# Arduino_Mega2560.net
KiCad netlist of a schematic drawn in Altium Designer
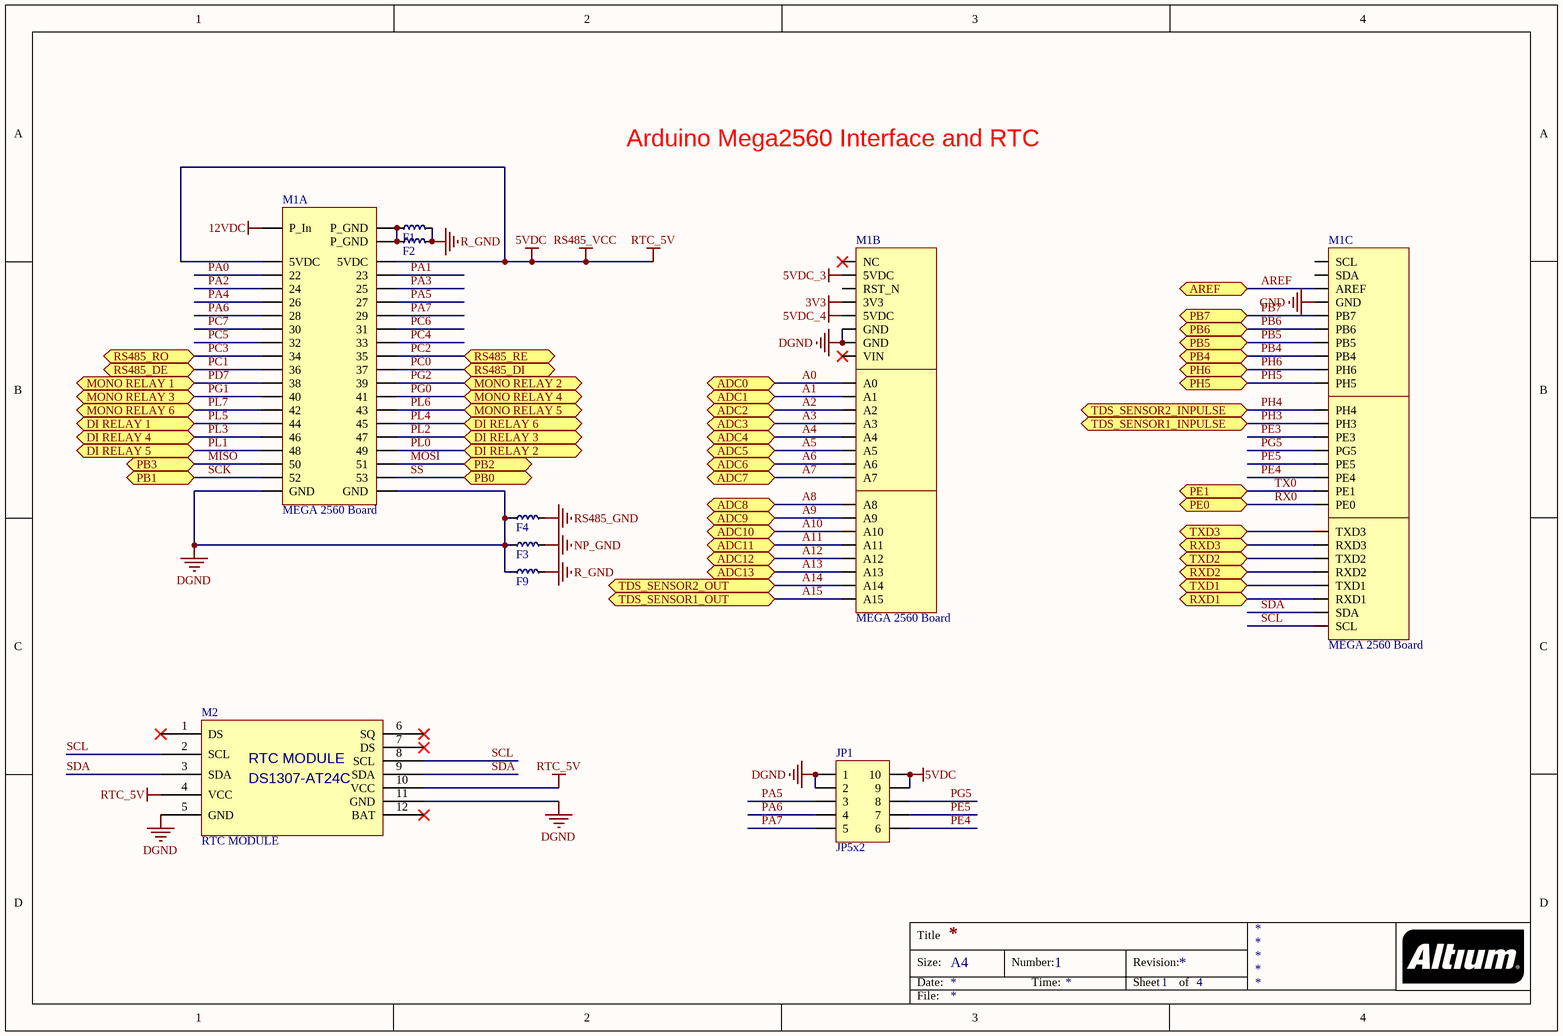
[diagram p0: Arduino_Mega2560.SchDoc]

(export (version "E")
  (design (tool "Eeschema 10.0.6"))
  (components
    (comp (ref "F1")
      (value "FBFB0805")
      (footprint "RESC_0603")
      (description "FERRITE BEAD 1000 OHM 0603")
      (libsource (lib "EngineersLife") (part "FB0603_1000Ohm"))
    )
    (comp (ref "F2")
      (value "FBFB0805")
      (footprint "RESC_0603")
      (description "FERRITE BEAD 1000 OHM 0603")
      (libsource (lib "EngineersLife") (part "FB0603_1000Ohm"))
    )
    (comp (ref "F3")
      (value "FBFB0805")
      (footprint "RESC_0603")
      (description "FERRITE BEAD 1000 OHM 0603")
      (libsource (lib "EngineersLife") (part "FB0603_1000Ohm"))
    )
    (comp (ref "F4")
      (value "FBFB0805")
      (footprint "RESC_0603")
      (description "FERRITE BEAD 1000 OHM 0603")
      (libsource (lib "EngineersLife") (part "FB0603_1000Ohm"))
    )
    (comp (ref "F9")
      (value "FBFB0805")
      (footprint "RESC_0603")
      (description "FERRITE BEAD 1000 OHM 0603")
      (libsource (lib "EngineersLife") (part "FB0603_1000Ohm"))
    )
    (comp (ref "JP1")
      (value "JP5x2")
      (footprint "JP5-D2T")
      (description "WR-PHD 2.54 mm Dual Socket Header")
      (fields
        (field (name "MANUFACTURER") "Würth Elektronik eiSos GmbH")
        (field (name "PARTNO") "61301021821")
        (field (name "CREATED BY") "Karrer Zheng")
      )
      (libsource (lib "EngineersLife") (part "JP5x2"))
    )
    (comp (ref "M1")
      (value "MEGA 2560 Board")
      (footprint "MEGA 2560")
      (description "Arduino ATMEGA 2560")
      (libsource (lib "EngineersLife") (part "MEGA 2560 Board"))
    )
    (comp (ref "M2")
      (value "RTC MODULE")
      (footprint "MODULE RTC DS1307-AT24C")
      (description "RTC DS1307-AT24C")
      (libsource (lib "EngineersLife") (part "RTC DS1307-AR24C"))
    )
  )
  (nets
    (net (code "1") (name "/A0") (class "Default")
      (node (ref "M1") (pin "A0") (pinfunction "A0_A0") (pintype "passive"))
    )
    (net (code "2") (name "/A1") (class "Default")
      (node (ref "M1") (pin "A1") (pinfunction "A1_A1") (pintype "passive"))
    )
    (net (code "3") (name "/A2") (class "Default")
      (node (ref "M1") (pin "A2") (pinfunction "A2_A2") (pintype "passive"))
    )
    (net (code "4") (name "/A3") (class "Default")
      (node (ref "M1") (pin "A3") (pinfunction "A3_A3") (pintype "passive"))
    )
    (net (code "5") (name "/A4") (class "Default")
      (node (ref "M1") (pin "A4") (pinfunction "A4_A4") (pintype "passive"))
    )
    (net (code "6") (name "/A5") (class "Default")
      (node (ref "M1") (pin "A5") (pinfunction "A5_A5") (pintype "passive"))
    )
    (net (code "7") (name "/A6") (class "Default")
      (node (ref "M1") (pin "A6") (pinfunction "A6_A6") (pintype "passive"))
    )
    (net (code "8") (name "/A7") (class "Default")
      (node (ref "M1") (pin "A7") (pinfunction "A7_A7") (pintype "passive"))
    )
    (net (code "9") (name "/A8") (class "Default")
      (node (ref "M1") (pin "A8") (pinfunction "A8_A8") (pintype "passive"))
    )
    (net (code "10") (name "/A9") (class "Default")
      (node (ref "M1") (pin "A9") (pinfunction "A9_A9") (pintype "passive"))
    )
    (net (code "11") (name "/A10") (class "Default")
      (node (ref "M1") (pin "A10") (pinfunction "A10_A10") (pintype "passive"))
    )
    (net (code "12") (name "/A11") (class "Default")
      (node (ref "M1") (pin "A11") (pinfunction "A11_A11") (pintype "passive"))
    )
    (net (code "13") (name "/A12") (class "Default")
      (node (ref "M1") (pin "A12") (pinfunction "A12_A12") (pintype "passive"))
    )
    (net (code "14") (name "/A13") (class "Default")
      (node (ref "M1") (pin "A13") (pinfunction "A13_A13") (pintype "passive"))
    )
    (net (code "15") (name "/A14") (class "Default")
      (node (ref "M1") (pin "A14") (pinfunction "A14_A14") (pintype "passive"))
    )
    (net (code "16") (name "/A15") (class "Default")
      (node (ref "M1") (pin "A15") (pinfunction "A15_A15") (pintype "passive"))
    )
    (net (code "17") (name "/AREF") (class "Default")
      (node (ref "M1") (pin "AREF") (pinfunction "AREF_AREF") (pintype "passive"))
    )
    (net (code "18") (name "/MISO") (class "Default")
      (node (ref "M1") (pin "50") (pinfunction "50_50") (pintype "passive"))
    )
    (net (code "19") (name "/MOSI") (class "Default")
      (node (ref "M1") (pin "51") (pinfunction "51_51") (pintype "passive"))
    )
    (net (code "20") (name "/PA0") (class "Default")
      (node (ref "M1") (pin "22") (pinfunction "22_22") (pintype "passive"))
    )
    (net (code "21") (name "/PA1") (class "Default")
      (node (ref "M1") (pin "23") (pinfunction "23_23") (pintype "passive"))
    )
    (net (code "22") (name "/PA2") (class "Default")
      (node (ref "M1") (pin "24") (pinfunction "24_24") (pintype "passive"))
    )
    (net (code "23") (name "/PA3") (class "Default")
      (node (ref "M1") (pin "25") (pinfunction "25_25") (pintype "passive"))
    )
    (net (code "24") (name "/PA4") (class "Default")
      (node (ref "M1") (pin "26") (pinfunction "26_26") (pintype "passive"))
    )
    (net (code "25") (name "/PA5") (class "Default")
      (node (ref "JP1") (pin "3") (pinfunction "3_3") (pintype "passive"))
      (node (ref "M1") (pin "27") (pinfunction "27_27") (pintype "passive"))
    )
    (net (code "26") (name "/PA6") (class "Default")
      (node (ref "JP1") (pin "4") (pinfunction "4_4") (pintype "passive"))
      (node (ref "M1") (pin "28") (pinfunction "28_28") (pintype "passive"))
    )
    (net (code "27") (name "/PA7") (class "Default")
      (node (ref "JP1") (pin "5") (pinfunction "5_5") (pintype "passive"))
      (node (ref "M1") (pin "29") (pinfunction "29_29") (pintype "passive"))
    )
    (net (code "28") (name "/PB4") (class "Default")
      (node (ref "M1") (pin "10") (pinfunction "PB4_10") (pintype "passive"))
    )
    (net (code "29") (name "/PB5") (class "Default")
      (node (ref "M1") (pin "11") (pinfunction "PB5_11") (pintype "passive"))
    )
    (net (code "30") (name "/PB6") (class "Default")
      (node (ref "M1") (pin "12") (pinfunction "PB6_12") (pintype "passive"))
    )
    (net (code "31") (name "/PB7") (class "Default")
      (node (ref "M1") (pin "13") (pinfunction "PB7_13") (pintype "passive"))
    )
    (net (code "32") (name "/PC0") (class "Default")
      (node (ref "M1") (pin "37") (pinfunction "37_37") (pintype "passive"))
    )
    (net (code "33") (name "/PC1") (class "Default")
      (node (ref "M1") (pin "36") (pinfunction "36_36") (pintype "passive"))
    )
    (net (code "34") (name "/PC2") (class "Default")
      (node (ref "M1") (pin "35") (pinfunction "35_35") (pintype "passive"))
    )
    (net (code "35") (name "/PC3") (class "Default")
      (node (ref "M1") (pin "34") (pinfunction "34_34") (pintype "passive"))
    )
    (net (code "36") (name "/PC4") (class "Default")
      (node (ref "M1") (pin "33") (pinfunction "33_33") (pintype "passive"))
    )
    (net (code "37") (name "/PC5") (class "Default")
      (node (ref "M1") (pin "32") (pinfunction "32_32") (pintype "passive"))
    )
    (net (code "38") (name "/PC6") (class "Default")
      (node (ref "M1") (pin "31") (pinfunction "31_31") (pintype "passive"))
    )
    (net (code "39") (name "/PC7") (class "Default")
      (node (ref "M1") (pin "30") (pinfunction "30_30") (pintype "passive"))
    )
    (net (code "40") (name "/PD7") (class "Default")
      (node (ref "M1") (pin "38") (pinfunction "38_38") (pintype "passive"))
    )
    (net (code "41") (name "/PE3") (class "Default")
      (node (ref "M1") (pin "5") (pinfunction "PE3_5") (pintype "passive"))
    )
    (net (code "42") (name "/PE4") (class "Default")
      (node (ref "JP1") (pin "6") (pinfunction "6_6") (pintype "passive"))
      (node (ref "M1") (pin "2") (pinfunction "PE4_2") (pintype "passive"))
    )
    (net (code "43") (name "/PE5") (class "Default")
      (node (ref "JP1") (pin "7") (pinfunction "7_7") (pintype "passive"))
      (node (ref "M1") (pin "3") (pinfunction "PE5_3") (pintype "passive"))
    )
    (net (code "44") (name "/PG0") (class "Default")
      (node (ref "M1") (pin "41") (pinfunction "41_41") (pintype "passive"))
    )
    (net (code "45") (name "/PG1") (class "Default")
      (node (ref "M1") (pin "40") (pinfunction "40_40") (pintype "passive"))
    )
    (net (code "46") (name "/PG2") (class "Default")
      (node (ref "M1") (pin "39") (pinfunction "39_39") (pintype "passive"))
    )
    (net (code "47") (name "/PG5") (class "Default")
      (node (ref "JP1") (pin "8") (pinfunction "8_8") (pintype "passive"))
      (node (ref "M1") (pin "4") (pinfunction "PG5_4") (pintype "passive"))
    )
    (net (code "48") (name "/PH3") (class "Default")
      (node (ref "M1") (pin "6") (pinfunction "PH3_6") (pintype "passive"))
    )
    (net (code "49") (name "/PH4") (class "Default")
      (node (ref "M1") (pin "7") (pinfunction "PH4_7") (pintype "passive"))
    )
    (net (code "50") (name "/PH5") (class "Default")
      (node (ref "M1") (pin "8") (pinfunction "PH5_8") (pintype "passive"))
    )
    (net (code "51") (name "/PH6") (class "Default")
      (node (ref "M1") (pin "9") (pinfunction "PH6_9") (pintype "passive"))
    )
    (net (code "52") (name "/PL0") (class "Default")
      (node (ref "M1") (pin "49") (pinfunction "49_49") (pintype "passive"))
    )
    (net (code "53") (name "/PL1") (class "Default")
      (node (ref "M1") (pin "48") (pinfunction "48_48") (pintype "passive"))
    )
    (net (code "54") (name "/PL2") (class "Default")
      (node (ref "M1") (pin "47") (pinfunction "47_47") (pintype "passive"))
    )
    (net (code "55") (name "/PL3") (class "Default")
      (node (ref "M1") (pin "46") (pinfunction "46_46") (pintype "passive"))
    )
    (net (code "56") (name "/PL4") (class "Default")
      (node (ref "M1") (pin "45") (pinfunction "45_45") (pintype "passive"))
    )
    (net (code "57") (name "/PL5") (class "Default")
      (node (ref "M1") (pin "44") (pinfunction "44_44") (pintype "passive"))
    )
    (net (code "58") (name "/PL6") (class "Default")
      (node (ref "M1") (pin "43") (pinfunction "43_43") (pintype "passive"))
    )
    (net (code "59") (name "/PL7") (class "Default")
      (node (ref "M1") (pin "42") (pinfunction "42_42") (pintype "passive"))
    )
    (net (code "60") (name "/RX0") (class "Default")
      (node (ref "M1") (pin "0") (pinfunction "PE0_0") (pintype "passive"))
    )
    (net (code "61") (name "/RXD1") (class "Default")
      (node (ref "M1") (pin "19") (pinfunction "RXD1_19") (pintype "passive"))
    )
    (net (code "62") (name "/RXD2") (class "Default")
      (node (ref "M1") (pin "17") (pinfunction "RXD2_17") (pintype "passive"))
    )
    (net (code "63") (name "/RXD3") (class "Default")
      (node (ref "M1") (pin "15") (pinfunction "RXD3_15") (pintype "passive"))
    )
    (net (code "64") (name "/SCK") (class "Default")
      (node (ref "M1") (pin "52") (pinfunction "52_52") (pintype "passive"))
    )
    (net (code "65") (name "/SCL") (class "Default")
      (node (ref "M1") (pin "21") (pinfunction "SCL_21") (pintype "passive"))
      (node (ref "M2") (pin "2") (pinfunction "SCL_2") (pintype "passive"))
      (node (ref "M2") (pin "8") (pinfunction "SCL_8") (pintype "passive"))
    )
    (net (code "66") (name "/SDA") (class "Default")
      (node (ref "M1") (pin "20") (pinfunction "SDA_20") (pintype "passive"))
      (node (ref "M2") (pin "3") (pinfunction "SDA_3") (pintype "passive"))
      (node (ref "M2") (pin "9") (pinfunction "SDA_9") (pintype "passive"))
    )
    (net (code "67") (name "/SS") (class "Default")
      (node (ref "M1") (pin "53") (pinfunction "53_53") (pintype "passive"))
    )
    (net (code "68") (name "/TX0") (class "Default")
      (node (ref "M1") (pin "1") (pinfunction "PE1_1") (pintype "passive"))
    )
    (net (code "69") (name "/TXD1") (class "Default")
      (node (ref "M1") (pin "18") (pinfunction "TXD1_18") (pintype "passive"))
    )
    (net (code "70") (name "/TXD2") (class "Default")
      (node (ref "M1") (pin "16") (pinfunction "TXD2_16") (pintype "passive"))
    )
    (net (code "71") (name "/TXD3") (class "Default")
      (node (ref "M1") (pin "14") (pinfunction "TXD3_14") (pintype "passive"))
    )
    (net (code "72") (name "3V3") (class "Default")
      (node (ref "M1") (pin "3V1") (pinfunction "3V3_3V1") (pintype "passive"))
    )
    (net (code "73") (name "5VDC") (class "Default")
      (node (ref "JP1") (pin "10") (pinfunction "10_10") (pintype "passive"))
      (node (ref "JP1") (pin "9") (pinfunction "9_9") (pintype "passive"))
      (node (ref "M1") (pin "5V1") (pinfunction "5VDC_5V1") (pintype "passive"))
      (node (ref "M1") (pin "5V2") (pinfunction "5VDC_5V2") (pintype "passive"))
      (node (ref "M2") (pin "10") (pinfunction "VCC_10") (pintype "passive"))
      (node (ref "M2") (pin "4") (pinfunction "VCC_4") (pintype "passive"))
    )
    (net (code "74") (name "5VDC_3") (class "Default")
      (node (ref "M1") (pin "5V3") (pinfunction "5VDC_5V3") (pintype "passive"))
    )
    (net (code "75") (name "5VDC_4") (class "Default")
      (node (ref "M1") (pin "5V4") (pinfunction "5VDC_5V4") (pintype "passive"))
    )
    (net (code "76") (name "12VDC") (class "Default")
      (node (ref "M1") (pin "P_In") (pinfunction "P_In_P_In") (pintype "passive"))
    )
    (net (code "77") (name "DGND") (class "Default")
      (node (ref "F3") (pin "1") (pinfunction "1_1") (pintype "passive"))
      (node (ref "F4") (pin "1") (pinfunction "1_1") (pintype "passive"))
      (node (ref "F9") (pin "1") (pinfunction "1_1") (pintype "passive"))
      (node (ref "JP1") (pin "1") (pinfunction "1_1") (pintype "passive"))
      (node (ref "JP1") (pin "2") (pinfunction "2_2") (pintype "passive"))
      (node (ref "M1") (pin "G1") (pinfunction "GND_G1") (pintype "passive"))
      (node (ref "M1") (pin "G2") (pinfunction "GND_G2") (pintype "passive"))
      (node (ref "M1") (pin "G3") (pinfunction "GND_G3") (pintype "passive"))
      (node (ref "M1") (pin "G4") (pinfunction "GND_G4") (pintype "passive"))
      (node (ref "M2") (pin "11") (pinfunction "GND_11") (pintype "passive"))
      (node (ref "M2") (pin "5") (pinfunction "GND_5") (pintype "passive"))
    )
    (net (code "78") (name "GND") (class "Default")
      (node (ref "M1") (pin "G5") (pinfunction "GND_G5") (pintype "passive"))
    )
    (net (code "79") (name "NP_GND") (class "Default")
      (node (ref "F3") (pin "2") (pinfunction "2_2") (pintype "passive"))
    )
    (net (code "80") (name "Net-(F1-Pad1)") (class "Default")
      (node (ref "F1") (pin "1") (pinfunction "1_1") (pintype "passive"))
      (node (ref "F2") (pin "1") (pinfunction "1_1") (pintype "passive"))
      (node (ref "M1") (pin "PGND1") (pinfunction "P_GND_PGND1") (pintype "passive"))
      (node (ref "M1") (pin "PGND2") (pinfunction "P_GND_PGND2") (pintype "passive"))
    )
    (net (code "81") (name "RS485_GND") (class "Default")
      (node (ref "F4") (pin "2") (pinfunction "2_2") (pintype "passive"))
    )
    (net (code "82") (name "R_GND") (class "Default")
      (node (ref "F1") (pin "2") (pinfunction "2_2") (pintype "passive"))
      (node (ref "F2") (pin "2") (pinfunction "2_2") (pintype "passive"))
      (node (ref "F9") (pin "2") (pinfunction "2_2") (pintype "passive"))
    )
    (net (code "83") (name "unconnected-(M1-PadNC)") (class "Default")
      (node (ref "M1") (pin "NC") (pinfunction "NC_NC") (pintype "passive+no_connect"))
    )
    (net (code "84") (name "unconnected-(M1-PadSCL)") (class "Default")
      (node (ref "M1") (pin "SCL") (pinfunction "SCL_SCL") (pintype "passive"))
    )
    (net (code "85") (name "unconnected-(M1-PadSDA)") (class "Default")
      (node (ref "M1") (pin "SDA") (pinfunction "SDA_SDA") (pintype "passive"))
    )
    (net (code "86") (name "unconnected-(M1-PadVIN)") (class "Default")
      (node (ref "M1") (pin "VIN") (pinfunction "VIN_VIN") (pintype "passive+no_connect"))
    )
    (net (code "87") (name "unconnected-(M1B-RST_N-PadRST)") (class "Default")
      (node (ref "M1") (pin "RST") (pinfunction "RST_N_RST") (pintype "passive"))
    )
    (net (code "88") (name "unconnected-(M2-BAT-Pad12)") (class "Default")
      (node (ref "M2") (pin "12") (pinfunction "BAT_12") (pintype "passive+no_connect"))
    )
    (net (code "89") (name "unconnected-(M2-DS-Pad1)") (class "Default")
      (node (ref "M2") (pin "1") (pinfunction "DS_1") (pintype "passive+no_connect"))
    )
    (net (code "90") (name "unconnected-(M2-DS-Pad7)") (class "Default")
      (node (ref "M2") (pin "7") (pinfunction "DS_7") (pintype "passive+no_connect"))
    )
    (net (code "91") (name "unconnected-(M2-SQ-Pad6)") (class "Default")
      (node (ref "M2") (pin "6") (pinfunction "SQ_6") (pintype "passive+no_connect"))
    )
  )
)
